# RN487_dev_board.net
KiCad netlist of a schematic drawn in EAGLE
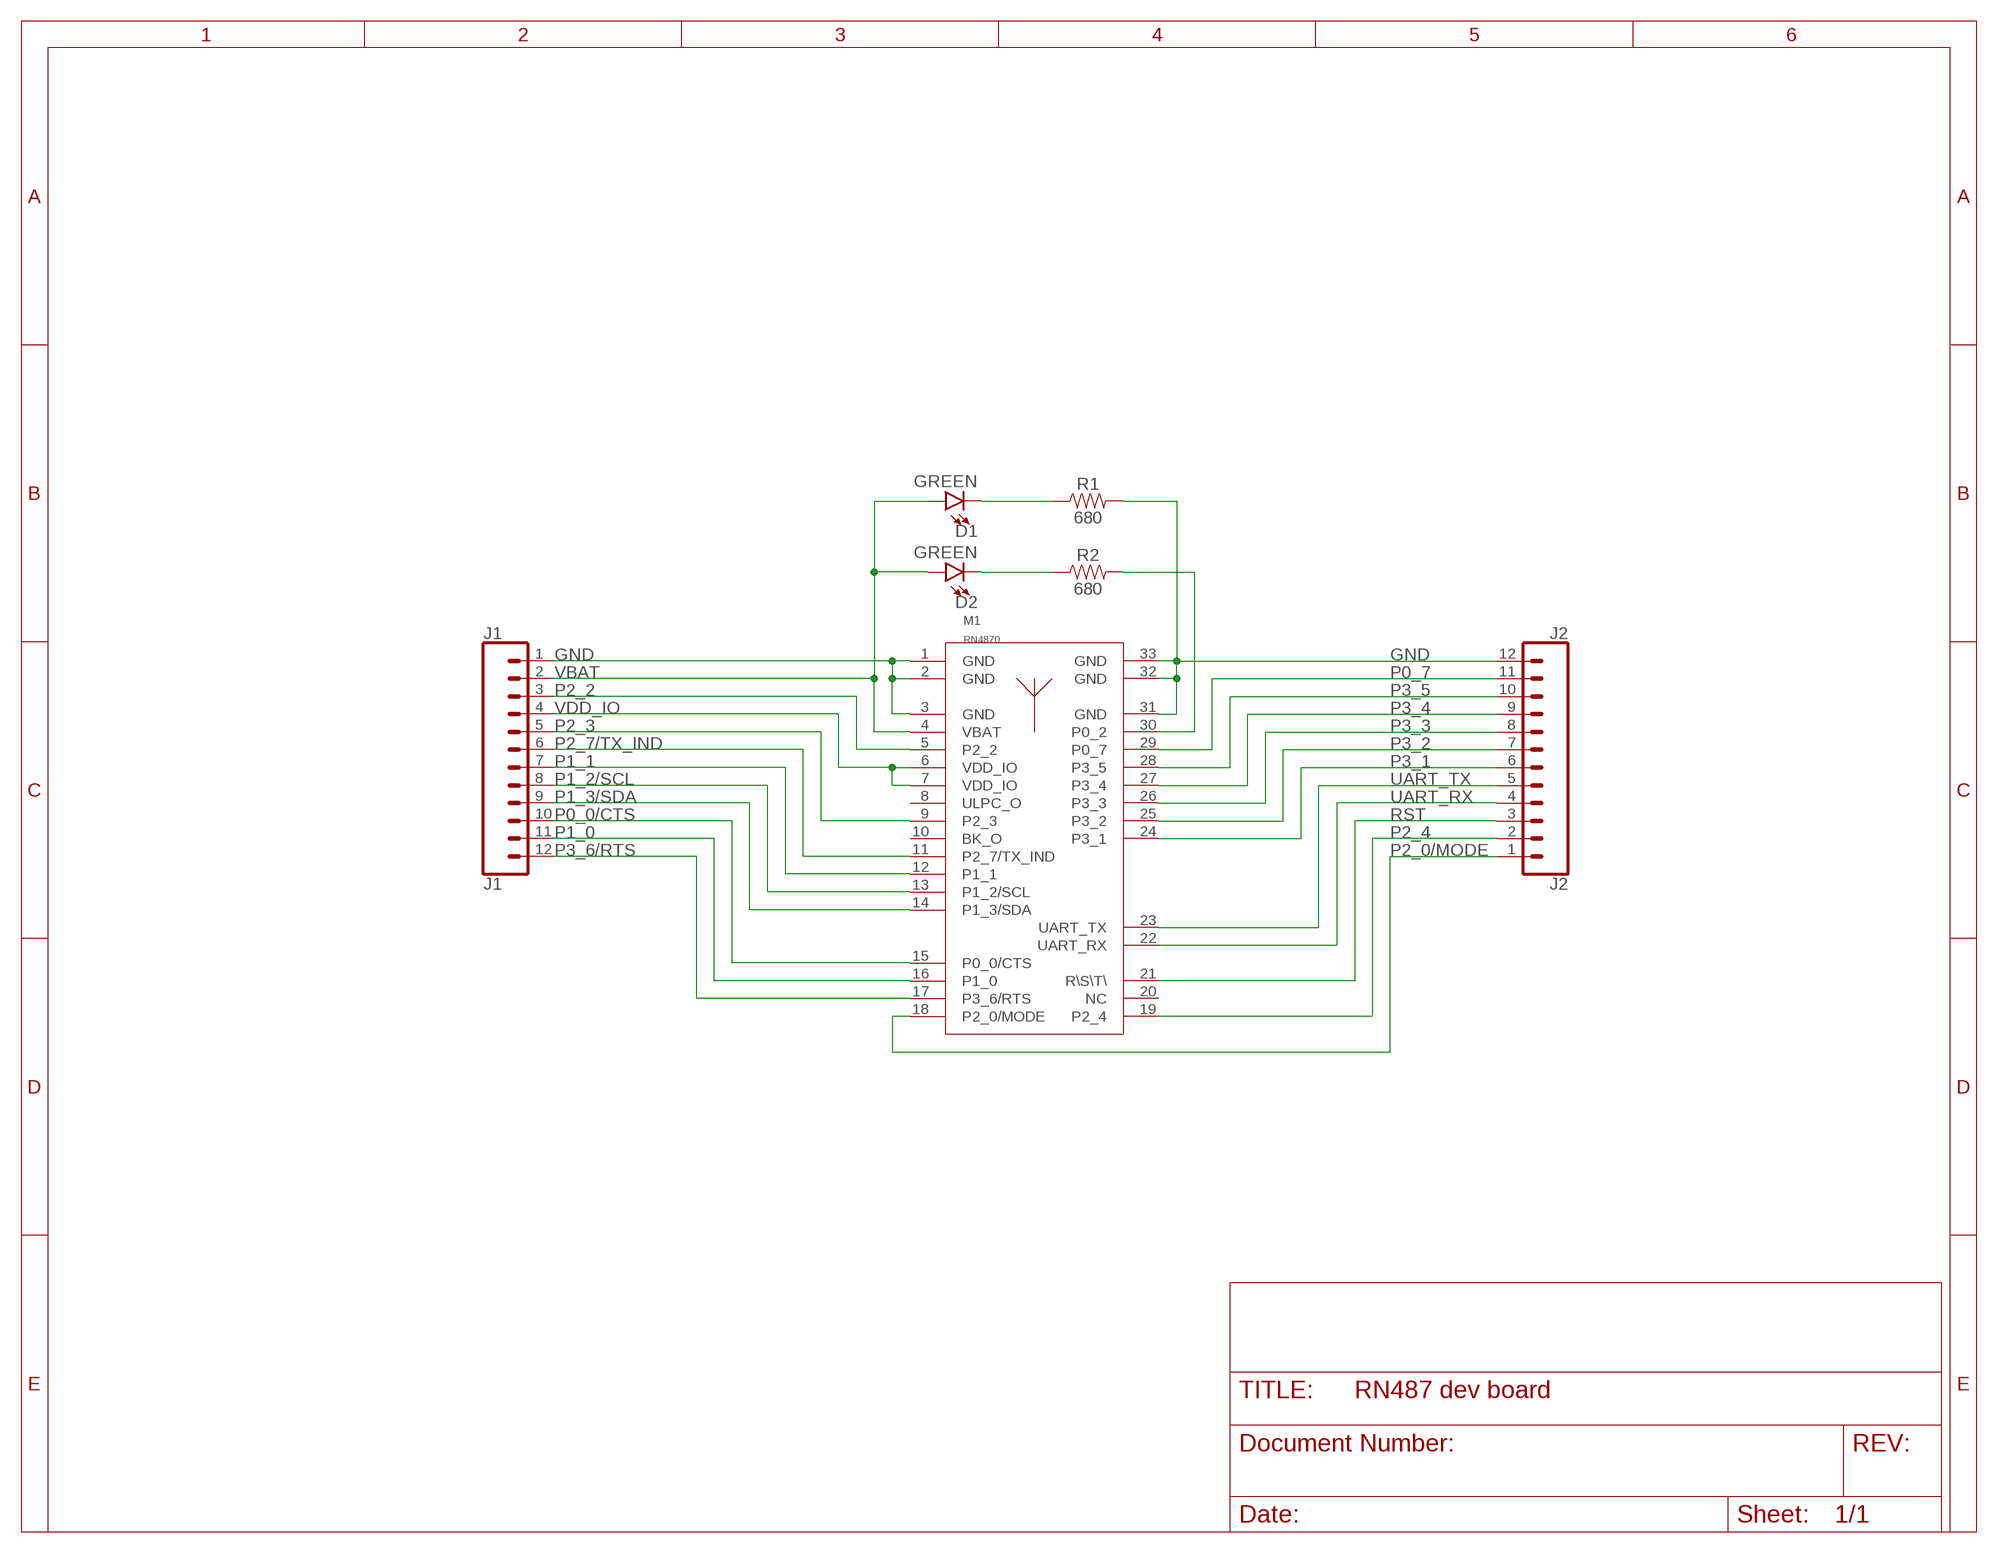
[diagram p0: schematic, sheet 1]

(export (version "E")
  (design (tool "Eeschema 10.0.6"))
  (components
    (comp (ref "D1")
      (value "GREEN")
      (footprint "eagle-import:LED-0603")
      (libsource (lib "eagle-import") (part "LED-GREEN0603"))
    )
    (comp (ref "D2")
      (value "GREEN")
      (footprint "eagle-import:LED-0603")
      (libsource (lib "eagle-import") (part "LED-GREEN0603"))
    )
    (comp (ref "J1")
      (value "J1")
      (footprint "eagle-import:1X12")
      (libsource (lib "eagle-import") (part "CONN_12"))
    )
    (comp (ref "J2")
      (value "J2")
      (footprint "eagle-import:1X12")
      (libsource (lib "eagle-import") (part "CONN_12"))
    )
    (comp (ref "M1")
      (value "RN4870")
      (footprint "eagle-import:RN4870")
      (libsource (lib "eagle-import") (part "RN4870"))
    )
    (comp (ref "R1")
      (value "680")
      (footprint "eagle-import:0603")
      (libsource (lib "eagle-import") (part "680OHM-0603-1/10W-5%"))
    )
    (comp (ref "R2")
      (value "680")
      (footprint "eagle-import:0603")
      (libsource (lib "eagle-import") (part "680OHM-0603-1/10W-5%"))
    )
  )
  (nets
    (net (code "1") (name "/GND") (class "Default")
      (node (ref "J1") (pin "1") (pinfunction "1_1") (pintype "passive"))
      (node (ref "J2") (pin "12") (pinfunction "12_12") (pintype "passive"))
      (node (ref "M1") (pin "1") (pinfunction "GND_1") (pintype "power_in"))
      (node (ref "M1") (pin "2") (pinfunction "GND_2") (pintype "power_in"))
      (node (ref "M1") (pin "3") (pinfunction "GND_3") (pintype "power_in"))
      (node (ref "M1") (pin "31") (pinfunction "GND_31") (pintype "power_in"))
      (node (ref "M1") (pin "32") (pinfunction "GND_32") (pintype "power_in"))
      (node (ref "M1") (pin "33") (pinfunction "GND_33") (pintype "power_in"))
      (node (ref "R1") (pin "2") (pinfunction "2_2") (pintype "passive"))
    )
    (net (code "2") (name "/P0_0{slash}CTS") (class "Default")
      (node (ref "J1") (pin "10") (pinfunction "10_10") (pintype "passive"))
      (node (ref "M1") (pin "15") (pinfunction "P0_0/CTS_15") (pintype "bidirectional"))
    )
    (net (code "3") (name "/P0_7") (class "Default")
      (node (ref "J2") (pin "11") (pinfunction "11_11") (pintype "passive"))
      (node (ref "M1") (pin "29") (pinfunction "P0_7_29") (pintype "bidirectional"))
    )
    (net (code "4") (name "/P1_0") (class "Default")
      (node (ref "J1") (pin "11") (pinfunction "11_11") (pintype "passive"))
      (node (ref "M1") (pin "16") (pinfunction "P1_0_16") (pintype "bidirectional"))
    )
    (net (code "5") (name "/P1_1") (class "Default")
      (node (ref "J1") (pin "7") (pinfunction "7_7") (pintype "passive"))
      (node (ref "M1") (pin "12") (pinfunction "P1_1_12") (pintype "bidirectional"))
    )
    (net (code "6") (name "/P1_2{slash}SCL") (class "Default")
      (node (ref "J1") (pin "8") (pinfunction "8_8") (pintype "passive"))
      (node (ref "M1") (pin "13") (pinfunction "P1_2/SCL_13") (pintype "bidirectional"))
    )
    (net (code "7") (name "/P1_3{slash}SDA") (class "Default")
      (node (ref "J1") (pin "9") (pinfunction "9_9") (pintype "passive"))
      (node (ref "M1") (pin "14") (pinfunction "P1_3/SDA_14") (pintype "bidirectional"))
    )
    (net (code "8") (name "/P2_0{slash}MODE") (class "Default")
      (node (ref "J2") (pin "1") (pinfunction "1_1") (pintype "passive"))
      (node (ref "M1") (pin "18") (pinfunction "P2_0/MODE_18") (pintype "input"))
    )
    (net (code "9") (name "/P2_2") (class "Default")
      (node (ref "J1") (pin "3") (pinfunction "3_3") (pintype "passive"))
      (node (ref "M1") (pin "5") (pinfunction "P2_2_5") (pintype "bidirectional"))
    )
    (net (code "10") (name "/P2_3") (class "Default")
      (node (ref "J1") (pin "5") (pinfunction "5_5") (pintype "passive"))
      (node (ref "M1") (pin "9") (pinfunction "P2_3_9") (pintype "input"))
    )
    (net (code "11") (name "/P2_4") (class "Default")
      (node (ref "J2") (pin "2") (pinfunction "2_2") (pintype "passive"))
      (node (ref "M1") (pin "19") (pinfunction "P2_4_19") (pintype "bidirectional"))
    )
    (net (code "12") (name "/P2_7{slash}TX_IND") (class "Default")
      (node (ref "J1") (pin "6") (pinfunction "6_6") (pintype "passive"))
      (node (ref "M1") (pin "11") (pinfunction "P2_7/TX_IND_11") (pintype "bidirectional"))
    )
    (net (code "13") (name "/P3_1") (class "Default")
      (node (ref "J2") (pin "6") (pinfunction "6_6") (pintype "passive"))
      (node (ref "M1") (pin "24") (pinfunction "P3_1_24") (pintype "bidirectional"))
    )
    (net (code "14") (name "/P3_2") (class "Default")
      (node (ref "J2") (pin "7") (pinfunction "7_7") (pintype "passive"))
      (node (ref "M1") (pin "25") (pinfunction "P3_2_25") (pintype "bidirectional"))
    )
    (net (code "15") (name "/P3_3") (class "Default")
      (node (ref "J2") (pin "8") (pinfunction "8_8") (pintype "passive"))
      (node (ref "M1") (pin "26") (pinfunction "P3_3_26") (pintype "bidirectional"))
    )
    (net (code "16") (name "/P3_4") (class "Default")
      (node (ref "J2") (pin "9") (pinfunction "9_9") (pintype "passive"))
      (node (ref "M1") (pin "27") (pinfunction "P3_4_27") (pintype "bidirectional"))
    )
    (net (code "17") (name "/P3_5") (class "Default")
      (node (ref "J2") (pin "10") (pinfunction "10_10") (pintype "passive"))
      (node (ref "M1") (pin "28") (pinfunction "P3_5_28") (pintype "bidirectional"))
    )
    (net (code "18") (name "/P3_6{slash}RTS") (class "Default")
      (node (ref "J1") (pin "12") (pinfunction "12_12") (pintype "passive"))
      (node (ref "M1") (pin "17") (pinfunction "P3_6/RTS_17") (pintype "bidirectional"))
    )
    (net (code "19") (name "/RST") (class "Default")
      (node (ref "J2") (pin "3") (pinfunction "3_3") (pintype "passive"))
      (node (ref "M1") (pin "21") (pinfunction "R\\S\\T\\_21") (pintype "input"))
    )
    (net (code "20") (name "/UART_RX") (class "Default")
      (node (ref "J2") (pin "4") (pinfunction "4_4") (pintype "passive"))
      (node (ref "M1") (pin "22") (pinfunction "UART_RX_22") (pintype "input"))
    )
    (net (code "21") (name "/UART_TX") (class "Default")
      (node (ref "J2") (pin "5") (pinfunction "5_5") (pintype "passive"))
      (node (ref "M1") (pin "23") (pinfunction "UART_TX_23") (pintype "output"))
    )
    (net (code "22") (name "/VBAT") (class "Default")
      (node (ref "D1") (pin "A") (pinfunction "A_A") (pintype "passive"))
      (node (ref "D2") (pin "A") (pinfunction "A_A") (pintype "passive"))
      (node (ref "J1") (pin "2") (pinfunction "2_2") (pintype "passive"))
      (node (ref "M1") (pin "4") (pinfunction "VBAT_4") (pintype "power_in"))
    )
    (net (code "23") (name "/VDD_IO") (class "Default")
      (node (ref "J1") (pin "4") (pinfunction "4_4") (pintype "passive"))
      (node (ref "M1") (pin "6") (pinfunction "VDD_IO_6") (pintype "power_in"))
      (node (ref "M1") (pin "7") (pinfunction "VDD_IO_7") (pintype "power_in"))
    )
    (net (code "24") (name "Net-(D1-PadC)") (class "Default")
      (node (ref "D1") (pin "C") (pinfunction "C_C") (pintype "passive"))
      (node (ref "R1") (pin "1") (pinfunction "1_1") (pintype "passive"))
    )
    (net (code "25") (name "Net-(D2-PadC)") (class "Default")
      (node (ref "D2") (pin "C") (pinfunction "C_C") (pintype "passive"))
      (node (ref "R2") (pin "1") (pinfunction "1_1") (pintype "passive"))
    )
    (net (code "26") (name "Net-(M1-P0_2)") (class "Default")
      (node (ref "M1") (pin "30") (pinfunction "P0_2_30") (pintype "bidirectional"))
      (node (ref "R2") (pin "2") (pinfunction "2_2") (pintype "passive"))
    )
    (net (code "27") (name "unconnected-(M1-BK_O-Pad10)") (class "Default")
      (node (ref "M1") (pin "10") (pinfunction "BK_O_10") (pintype "passive"))
    )
    (net (code "28") (name "unconnected-(M1-NC-Pad20)") (class "Default")
      (node (ref "M1") (pin "20") (pinfunction "NC_20") (pintype "passive"))
    )
    (net (code "29") (name "unconnected-(M1-ULPC_O-Pad8)") (class "Default")
      (node (ref "M1") (pin "8") (pinfunction "ULPC_O_8") (pintype "passive"))
    )
  )
)
